# HoneyBee-V1_2.net
KiCad netlist of a schematic drawn in EAGLE
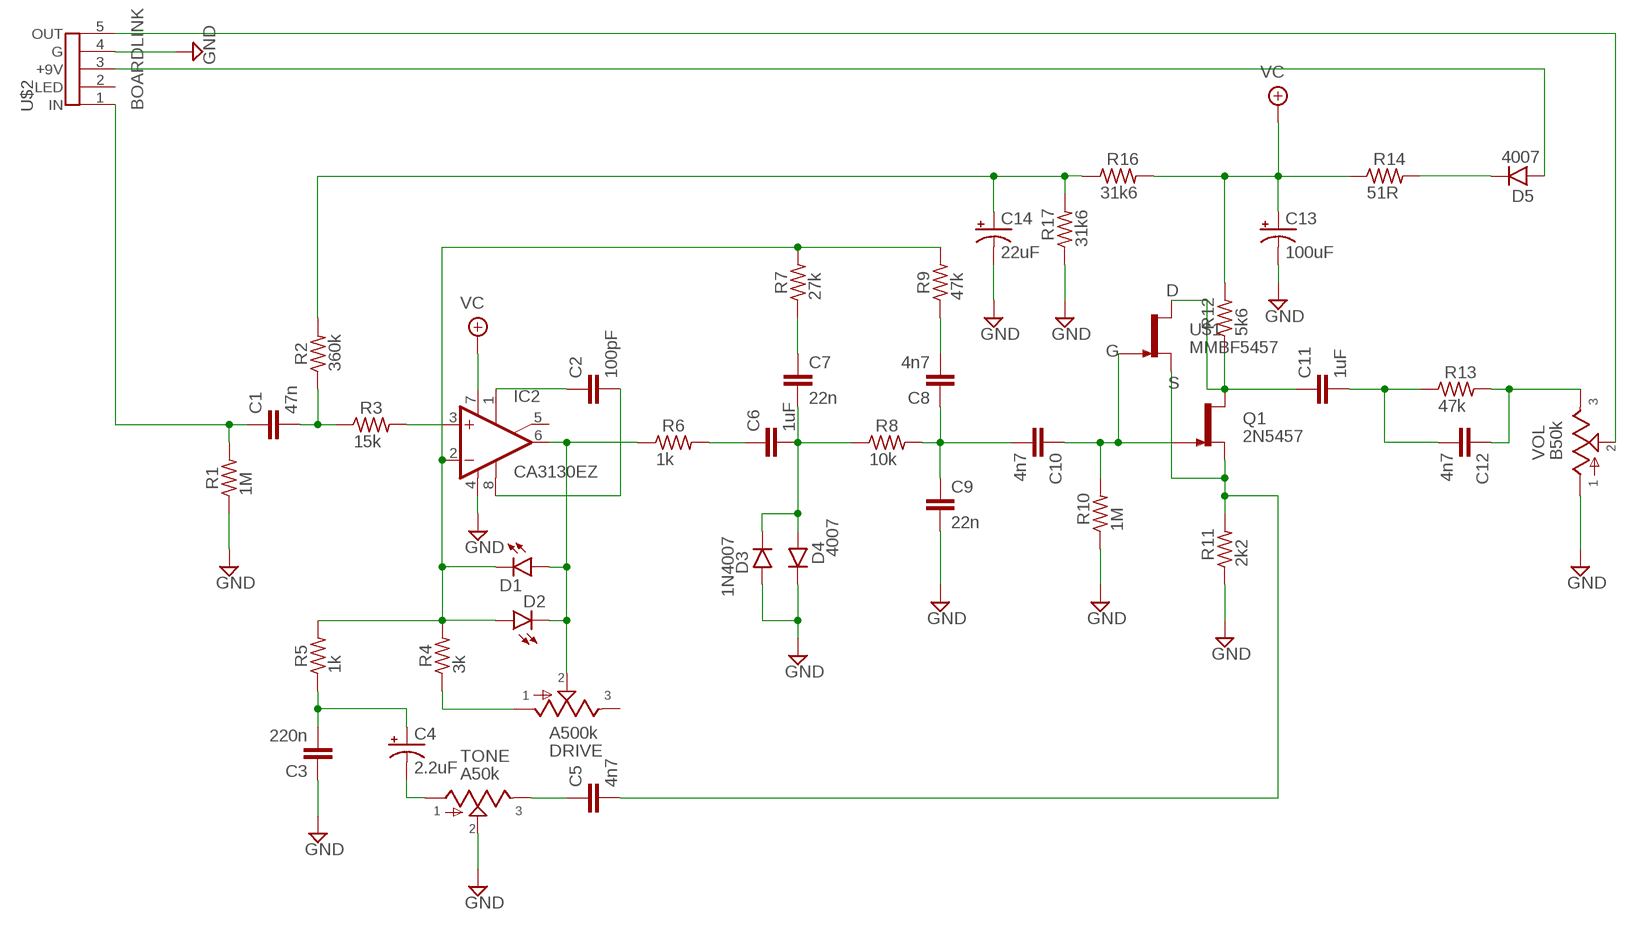
[diagram p0: schematic, sheet 1]

(export (version "E")
  (design (tool "Eeschema 10.0.6"))
  (components
    (comp (ref "C1")
      (value "47n")
      (footprint "eagle-import:075X040")
      (libsource (lib "eagle-import") (part "075X0402"))
    )
    (comp (ref "C2")
      (value "100pF")
      (footprint "eagle-import:050X030_025")
      (libsource (lib "eagle-import") (part "050X030_0251"))
    )
    (comp (ref "C3")
      (value "220n")
      (footprint "eagle-import:080X050")
      (libsource (lib "eagle-import") (part "080X0502"))
    )
    (comp (ref "C4")
      (value "2.2uF")
      (footprint "eagle-import:050_020_1")
      (libsource (lib "eagle-import") (part "0501"))
    )
    (comp (ref "C5")
      (value "4n7")
      (footprint "eagle-import:070X030")
      (libsource (lib "eagle-import") (part "070X0302"))
    )
    (comp (ref "C6")
      (value "1uF")
      (footprint "eagle-import:080X050")
      (libsource (lib "eagle-import") (part "080X0502"))
    )
    (comp (ref "C7")
      (value "22n")
      (footprint "eagle-import:075X030")
      (libsource (lib "eagle-import") (part "075X0302"))
    )
    (comp (ref "C8")
      (value "4n7")
      (footprint "eagle-import:070X030")
      (libsource (lib "eagle-import") (part "070X0302"))
    )
    (comp (ref "C9")
      (value "22n")
      (footprint "eagle-import:075X030")
      (libsource (lib "eagle-import") (part "075X0302"))
    )
    (comp (ref "C10")
      (value "4n7")
      (footprint "eagle-import:070X030")
      (libsource (lib "eagle-import") (part "070X0302"))
    )
    (comp (ref "C11")
      (value "1uF")
      (footprint "eagle-import:080X050")
      (libsource (lib "eagle-import") (part "080X0502"))
    )
    (comp (ref "C12")
      (value "4n7")
      (footprint "eagle-import:070X030")
      (libsource (lib "eagle-import") (part "070X0302"))
    )
    (comp (ref "C13")
      (value "100uF")
      (footprint "eagle-import:080_035_1")
      (libsource (lib "eagle-import") (part "0801"))
    )
    (comp (ref "C14")
      (value "22uF")
      (footprint "eagle-import:050_020_1")
      (libsource (lib "eagle-import") (part "0501"))
    )
    (comp (ref "D1")
      (value "LED3MM")
      (footprint "eagle-import:LED3MM")
      (libsource (lib "eagle-import") (part "LED3MM"))
    )
    (comp (ref "D2")
      (value "LED3MM")
      (footprint "eagle-import:LED3MM")
      (libsource (lib "eagle-import") (part "LED3MM"))
    )
    (comp (ref "D3")
      (value "1N4007")
      (footprint "eagle-import:DO41-3")
      (libsource (lib "eagle-import") (part "1N400X.3"))
    )
    (comp (ref "D4")
      (value "4007")
      (footprint "eagle-import:DO41-3")
      (libsource (lib "eagle-import") (part "1N400X.3"))
    )
    (comp (ref "D5")
      (value "4007")
      (footprint "eagle-import:DO41-3")
      (libsource (lib "eagle-import") (part "1N400X.3"))
    )
    (comp (ref "DRIVE")
      (value "A500k")
      (footprint "eagle-import:16MM")
      (libsource (lib "eagle-import") (part "POT16MM"))
    )
    (comp (ref "IC2")
      (value "CA3130EZ")
      (footprint "eagle-import:DIL08")
      (libsource (lib "eagle-import") (part "CA3130EZPLM"))
    )
    (comp (ref "Q1")
      (value "2N5457")
      (footprint "eagle-import:TO92-")
      (libsource (lib "eagle-import") (part "2N5457"))
    )
    (comp (ref "R1")
      (value "1M")
      (footprint "eagle-import:R0207_3")
      (libsource (lib "eagle-import") (part "6MM.3"))
    )
    (comp (ref "R2")
      (value "360k")
      (footprint "eagle-import:R0207_3")
      (libsource (lib "eagle-import") (part "6MM.3"))
    )
    (comp (ref "R3")
      (value "15k")
      (footprint "eagle-import:R0207_3")
      (libsource (lib "eagle-import") (part "6MM.3"))
    )
    (comp (ref "R4")
      (value "3k")
      (footprint "eagle-import:R0207_3")
      (libsource (lib "eagle-import") (part "6MM.3"))
    )
    (comp (ref "R5")
      (value "1k")
      (footprint "eagle-import:R0207_3")
      (libsource (lib "eagle-import") (part "6MM.3"))
    )
    (comp (ref "R6")
      (value "1k")
      (footprint "eagle-import:R0207_3")
      (libsource (lib "eagle-import") (part "6MM.3"))
    )
    (comp (ref "R7")
      (value "27k")
      (footprint "eagle-import:R0207_3")
      (libsource (lib "eagle-import") (part "6MM.3"))
    )
    (comp (ref "R8")
      (value "10k")
      (footprint "eagle-import:R0207_3")
      (libsource (lib "eagle-import") (part "6MM.3"))
    )
    (comp (ref "R9")
      (value "47k")
      (footprint "eagle-import:R0207_3")
      (libsource (lib "eagle-import") (part "6MM.3"))
    )
    (comp (ref "R10")
      (value "1M")
      (footprint "eagle-import:R0207_3")
      (libsource (lib "eagle-import") (part "6MM.3"))
    )
    (comp (ref "R11")
      (value "2k2")
      (footprint "eagle-import:R0207_3")
      (libsource (lib "eagle-import") (part "6MM.3"))
    )
    (comp (ref "R12")
      (value "5k6")
      (footprint "eagle-import:R0207_3")
      (libsource (lib "eagle-import") (part "6MM.3"))
    )
    (comp (ref "R13")
      (value "47k")
      (footprint "eagle-import:R0207_3")
      (libsource (lib "eagle-import") (part "6MM.3"))
    )
    (comp (ref "R14")
      (value "51R")
      (footprint "eagle-import:R0207_3")
      (libsource (lib "eagle-import") (part "6MM.3"))
    )
    (comp (ref "R16")
      (value "31k6")
      (footprint "eagle-import:R0207_3")
      (libsource (lib "eagle-import") (part "6MM.3"))
    )
    (comp (ref "R17")
      (value "31k6")
      (footprint "eagle-import:R0207_3")
      (libsource (lib "eagle-import") (part "6MM.3"))
    )
    (comp (ref "TONE")
      (value "A50k")
      (footprint "eagle-import:16MM")
      (libsource (lib "eagle-import") (part "POT16MM"))
    )
    (comp (ref "U$1")
      (value "MMBF5457")
      (footprint "eagle-import:SOT23")
      (libsource (lib "eagle-import") (part "MMBF5457"))
    )
    (comp (ref "U$2")
      (value "BOARDLINK")
      (footprint "eagle-import:BOARDLINK")
      (libsource (lib "eagle-import") (part "BOARDLINK"))
    )
    (comp (ref "VOL")
      (value "B50k")
      (footprint "eagle-import:16MM")
      (libsource (lib "eagle-import") (part "POT16MM"))
    )
  )
  (nets
    (net (code "1") (name "GND") (class "Default")
      (node (ref "C13") (pin "-") (pinfunction "-_-") (pintype "passive"))
      (node (ref "C14") (pin "-") (pinfunction "-_-") (pintype "passive"))
      (node (ref "C3") (pin "1") (pinfunction "1_1") (pintype "passive"))
      (node (ref "C9") (pin "2") (pinfunction "2_2") (pintype "passive"))
      (node (ref "D3") (pin "A") (pinfunction "A_A") (pintype "passive"))
      (node (ref "D4") (pin "C") (pinfunction "C_C") (pintype "passive"))
      (node (ref "IC2") (pin "4") (pinfunction "V-_4") (pintype "power_in"))
      (node (ref "R1") (pin "1") (pinfunction "1_1") (pintype "passive"))
      (node (ref "R10") (pin "1") (pinfunction "1_1") (pintype "passive"))
      (node (ref "R11") (pin "1") (pinfunction "1_1") (pintype "passive"))
      (node (ref "R17") (pin "1") (pinfunction "1_1") (pintype "passive"))
      (node (ref "TONE") (pin "2") (pinfunction "2_2") (pintype "passive"))
      (node (ref "U$2") (pin "4") (pinfunction "G_4") (pintype "bidirectional"))
      (node (ref "VOL") (pin "1") (pinfunction "1_1") (pintype "passive"))
    )
    (net (code "2") (name "Net-(C1-Pad2)") (class "Default")
      (node (ref "C1") (pin "2") (pinfunction "2_2") (pintype "passive"))
      (node (ref "R2") (pin "1") (pinfunction "1_1") (pintype "passive"))
      (node (ref "R3") (pin "1") (pinfunction "1_1") (pintype "passive"))
    )
    (net (code "3") (name "Net-(C3-Pad2)") (class "Default")
      (node (ref "C3") (pin "2") (pinfunction "2_2") (pintype "passive"))
      (node (ref "C4") (pin "+") (pinfunction "+_+") (pintype "passive"))
      (node (ref "R5") (pin "1") (pinfunction "1_1") (pintype "passive"))
    )
    (net (code "4") (name "Net-(C4-Pad-)") (class "Default")
      (node (ref "C4") (pin "-") (pinfunction "-_-") (pintype "passive"))
      (node (ref "TONE") (pin "1") (pinfunction "1_1") (pintype "passive"))
    )
    (net (code "5") (name "Net-(C5-Pad1)") (class "Default")
      (node (ref "C5") (pin "1") (pinfunction "1_1") (pintype "passive"))
      (node (ref "TONE") (pin "3") (pinfunction "3_3") (pintype "passive"))
    )
    (net (code "6") (name "Net-(C6-Pad1)") (class "Default")
      (node (ref "C6") (pin "1") (pinfunction "1_1") (pintype "passive"))
      (node (ref "R6") (pin "2") (pinfunction "2_2") (pintype "passive"))
    )
    (net (code "7") (name "Net-(C6-Pad2)") (class "Default")
      (node (ref "C6") (pin "2") (pinfunction "2_2") (pintype "passive"))
      (node (ref "C7") (pin "2") (pinfunction "2_2") (pintype "passive"))
      (node (ref "D3") (pin "C") (pinfunction "C_C") (pintype "passive"))
      (node (ref "D4") (pin "A") (pinfunction "A_A") (pintype "passive"))
      (node (ref "R8") (pin "1") (pinfunction "1_1") (pintype "passive"))
    )
    (net (code "8") (name "Net-(C7-Pad1)") (class "Default")
      (node (ref "C7") (pin "1") (pinfunction "1_1") (pintype "passive"))
      (node (ref "R7") (pin "1") (pinfunction "1_1") (pintype "passive"))
    )
    (net (code "9") (name "Net-(C8-Pad2)") (class "Default")
      (node (ref "C8") (pin "2") (pinfunction "2_2") (pintype "passive"))
      (node (ref "R9") (pin "1") (pinfunction "1_1") (pintype "passive"))
    )
    (net (code "10") (name "Net-(C10-Pad2)") (class "Default")
      (node (ref "C10") (pin "2") (pinfunction "2_2") (pintype "passive"))
      (node (ref "C8") (pin "1") (pinfunction "1_1") (pintype "passive"))
      (node (ref "C9") (pin "1") (pinfunction "1_1") (pintype "passive"))
      (node (ref "R8") (pin "2") (pinfunction "2_2") (pintype "passive"))
    )
    (net (code "11") (name "Net-(C11-Pad2)") (class "Default")
      (node (ref "C11") (pin "2") (pinfunction "2_2") (pintype "passive"))
      (node (ref "C12") (pin "2") (pinfunction "2_2") (pintype "passive"))
      (node (ref "R13") (pin "1") (pinfunction "1_1") (pintype "passive"))
    )
    (net (code "12") (name "Net-(C12-Pad1)") (class "Default")
      (node (ref "C12") (pin "1") (pinfunction "1_1") (pintype "passive"))
      (node (ref "R13") (pin "2") (pinfunction "2_2") (pintype "passive"))
      (node (ref "VOL") (pin "3") (pinfunction "3_3") (pintype "passive"))
    )
    (net (code "13") (name "Net-(C14-Pad+)") (class "Default")
      (node (ref "C14") (pin "+") (pinfunction "+_+") (pintype "passive"))
      (node (ref "R16") (pin "1") (pinfunction "1_1") (pintype "passive"))
      (node (ref "R17") (pin "2") (pinfunction "2_2") (pintype "passive"))
      (node (ref "R2") (pin "2") (pinfunction "2_2") (pintype "passive"))
    )
    (net (code "14") (name "Net-(D1-C)") (class "Default")
      (node (ref "D1") (pin "K") (pinfunction "C_K") (pintype "passive"))
      (node (ref "D2") (pin "A") (pinfunction "A_A") (pintype "passive"))
      (node (ref "IC2") (pin "2") (pinfunction "-IN_2") (pintype "input"))
      (node (ref "R4") (pin "2") (pinfunction "2_2") (pintype "passive"))
      (node (ref "R5") (pin "2") (pinfunction "2_2") (pintype "passive"))
      (node (ref "R7") (pin "2") (pinfunction "2_2") (pintype "passive"))
      (node (ref "R9") (pin "2") (pinfunction "2_2") (pintype "passive"))
    )
    (net (code "15") (name "Net-(D2-C)") (class "Default")
      (node (ref "D1") (pin "A") (pinfunction "A_A") (pintype "passive"))
      (node (ref "D2") (pin "K") (pinfunction "C_K") (pintype "passive"))
      (node (ref "DRIVE") (pin "2") (pinfunction "2_2") (pintype "passive"))
      (node (ref "IC2") (pin "6") (pinfunction "OUT_6") (pintype "output"))
      (node (ref "R6") (pin "1") (pinfunction "1_1") (pintype "passive"))
    )
    (net (code "16") (name "Net-(D5-PadC)") (class "Default")
      (node (ref "D5") (pin "C") (pinfunction "C_C") (pintype "passive"))
      (node (ref "R14") (pin "2") (pinfunction "2_2") (pintype "passive"))
    )
    (net (code "17") (name "Net-(DRIVE-Pad1)") (class "Default")
      (node (ref "DRIVE") (pin "1") (pinfunction "1_1") (pintype "passive"))
      (node (ref "R4") (pin "1") (pinfunction "1_1") (pintype "passive"))
    )
    (net (code "18") (name "Net-(IC2-+IN)") (class "Default")
      (node (ref "IC2") (pin "3") (pinfunction "+IN_3") (pintype "input"))
      (node (ref "R3") (pin "2") (pinfunction "2_2") (pintype "passive"))
    )
    (net (code "19") (name "Net-(IC2-ON1)") (class "Default")
      (node (ref "C2") (pin "1") (pinfunction "1_1") (pintype "passive"))
      (node (ref "IC2") (pin "1") (pinfunction "ON1_1") (pintype "passive"))
    )
    (net (code "20") (name "Net-(IC2-OPT)") (class "Default")
      (node (ref "C2") (pin "2") (pinfunction "2_2") (pintype "passive"))
      (node (ref "IC2") (pin "8") (pinfunction "OPT_8") (pintype "passive"))
    )
    (net (code "21") (name "Net-(Q1-D)") (class "Default")
      (node (ref "C11") (pin "1") (pinfunction "1_1") (pintype "passive"))
      (node (ref "Q1") (pin "3") (pinfunction "D_3") (pintype "passive"))
      (node (ref "R12") (pin "1") (pinfunction "1_1") (pintype "passive"))
      (node (ref "U$1") (pin "1") (pinfunction "D_1") (pintype "passive"))
    )
    (net (code "22") (name "Net-(Q1-G)") (class "Default")
      (node (ref "C10") (pin "1") (pinfunction "1_1") (pintype "passive"))
      (node (ref "Q1") (pin "1") (pinfunction "G_1") (pintype "passive"))
      (node (ref "R10") (pin "2") (pinfunction "2_2") (pintype "passive"))
      (node (ref "U$1") (pin "3") (pinfunction "G_3") (pintype "passive"))
    )
    (net (code "23") (name "Net-(Q1-S)") (class "Default")
      (node (ref "C5") (pin "2") (pinfunction "2_2") (pintype "passive"))
      (node (ref "Q1") (pin "2") (pinfunction "S_2") (pintype "passive"))
      (node (ref "R11") (pin "2") (pinfunction "2_2") (pintype "passive"))
      (node (ref "U$1") (pin "2") (pinfunction "S_2") (pintype "passive"))
    )
    (net (code "24") (name "Net-(U$2-+9V)") (class "Default")
      (node (ref "D5") (pin "A") (pinfunction "A_A") (pintype "passive"))
      (node (ref "U$2") (pin "3") (pinfunction "+9V_3") (pintype "bidirectional"))
    )
    (net (code "25") (name "Net-(U$2-IN)") (class "Default")
      (node (ref "C1") (pin "1") (pinfunction "1_1") (pintype "passive"))
      (node (ref "R1") (pin "2") (pinfunction "2_2") (pintype "passive"))
      (node (ref "U$2") (pin "1") (pinfunction "IN_1") (pintype "bidirectional"))
    )
    (net (code "26") (name "Net-(U$2-OUT)") (class "Default")
      (node (ref "U$2") (pin "5") (pinfunction "OUT_5") (pintype "bidirectional"))
      (node (ref "VOL") (pin "2") (pinfunction "2_2") (pintype "passive"))
    )
    (net (code "27") (name "VC") (class "Default")
      (node (ref "C13") (pin "+") (pinfunction "+_+") (pintype "passive"))
      (node (ref "IC2") (pin "7") (pinfunction "V+_7") (pintype "power_in"))
      (node (ref "R12") (pin "2") (pinfunction "2_2") (pintype "passive"))
      (node (ref "R14") (pin "1") (pinfunction "1_1") (pintype "passive"))
      (node (ref "R16") (pin "2") (pinfunction "2_2") (pintype "passive"))
    )
    (net (code "28") (name "unconnected-(DRIVE-Pad3)") (class "Default")
      (node (ref "DRIVE") (pin "3") (pinfunction "3_3") (pintype "passive"))
    )
    (net (code "29") (name "unconnected-(IC2-ON2-Pad5)") (class "Default")
      (node (ref "IC2") (pin "5") (pinfunction "ON2_5") (pintype "passive"))
    )
    (net (code "30") (name "unconnected-(U$2-LED-Pad2)") (class "Default")
      (node (ref "U$2") (pin "2") (pinfunction "LED_2") (pintype "bidirectional"))
    )
  )
)
